# gps-breakout-mk-1_0.net
KiCad netlist of a schematic drawn in EAGLE
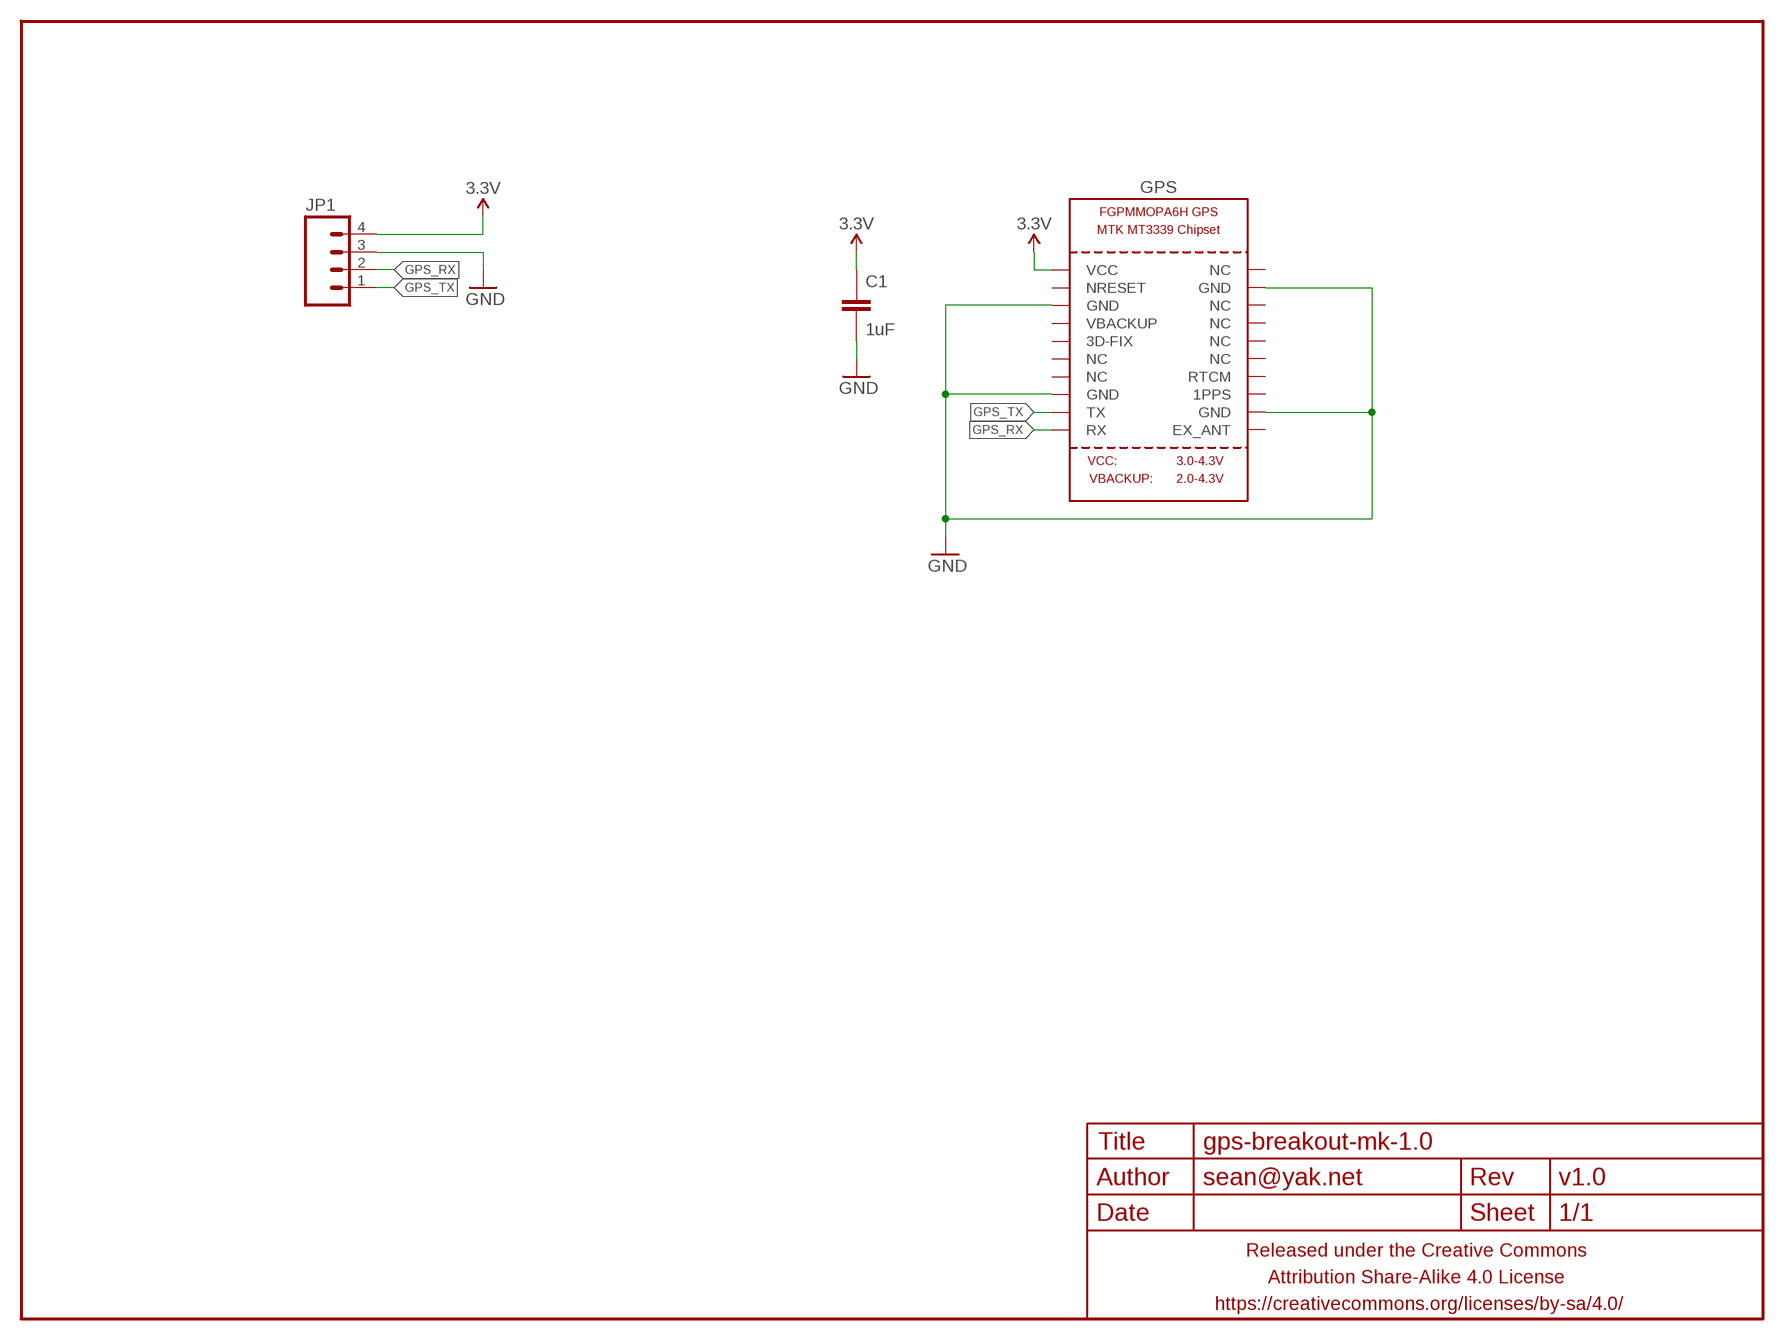
[diagram p0: schematic, sheet 1]

(export (version "E")
  (design (tool "Eeschema 10.0.6"))
  (components
    (comp (ref "C1")
      (value "1uF")
      (footprint "eagle-import:C0603")
      (libsource (lib "eagle-import") (part "CAPACITOR-CERAMICC0603"))
    )
    (comp (ref "FRAME1")
      (value "FRAME-LETTERNO_PACKAGE")
      (footprint "eagle-import:DUMMY")
      (fields (field (name "DESIGNER") "sean@yak.net") (field (name "VERSION") "v1.0"))
      (libsource (lib "eagle-import") (part "FRAME-LETTERNO_PACKAGE"))
    )
    (comp (ref "GPS")
      (value "GPS_FGPMMOPA6H")
      (footprint "eagle-import:FGPMMOPA6H")
      (libsource (lib "eagle-import") (part "GPS_FGPMMOPA6H"))
    )
    (comp (ref "JP1")
      (value "M04PTH-NS-CENTERED")
      (footprint "eagle-import:1X04-PTH-VERT-NS-CENTERED")
      (libsource (lib "eagle-import") (part "M04PTH-NS-CENTERED"))
    )
  )
  (nets
    (net (code "1") (name "3.3V") (class "Default")
      (node (ref "C1") (pin "1") (pinfunction "1_1") (pintype "passive"))
      (node (ref "GPS") (pin "P$1") (pinfunction "VCC_P$1") (pintype "bidirectional"))
      (node (ref "JP1") (pin "4") (pinfunction "4_4") (pintype "passive"))
    )
    (net (code "2") (name "GND") (class "Default")
      (node (ref "C1") (pin "2") (pinfunction "2_2") (pintype "passive"))
      (node (ref "GPS") (pin "P$12") (pinfunction "GND_P$12") (pintype "bidirectional"))
      (node (ref "GPS") (pin "P$19") (pinfunction "GND_P$19") (pintype "bidirectional"))
      (node (ref "GPS") (pin "P$3") (pinfunction "GND_P$3") (pintype "bidirectional"))
      (node (ref "GPS") (pin "P$8") (pinfunction "GND_P$8") (pintype "bidirectional"))
      (node (ref "JP1") (pin "3") (pinfunction "3_3") (pintype "passive"))
    )
    (net (code "3") (name "GPS_RX") (class "Default")
      (node (ref "GPS") (pin "P$10") (pinfunction "RX_P$10") (pintype "bidirectional"))
      (node (ref "JP1") (pin "2") (pinfunction "2_2") (pintype "passive"))
    )
    (net (code "4") (name "GPS_TX") (class "Default")
      (node (ref "GPS") (pin "P$9") (pinfunction "TX_P$9") (pintype "bidirectional"))
      (node (ref "JP1") (pin "1") (pinfunction "1_1") (pintype "passive"))
    )
    (net (code "5") (name "unconnected-(GPS-1PPS-PadP$13)") (class "Default")
      (node (ref "GPS") (pin "P$13") (pinfunction "1PPS_P$13") (pintype "bidirectional"))
    )
    (net (code "6") (name "unconnected-(GPS-3D-FIX-PadP$5)") (class "Default")
      (node (ref "GPS") (pin "P$5") (pinfunction "3D-FIX_P$5") (pintype "bidirectional"))
    )
    (net (code "7") (name "unconnected-(GPS-EX_ANT-PadP$11)") (class "Default")
      (node (ref "GPS") (pin "P$11") (pinfunction "EX_ANT_P$11") (pintype "bidirectional"))
    )
    (net (code "8") (name "unconnected-(GPS-NC-PadP$6)") (class "Default")
      (node (ref "GPS") (pin "P$6") (pinfunction "NC_P$6") (pintype "bidirectional"))
    )
    (net (code "9") (name "unconnected-(GPS-NC-PadP$7)") (class "Default")
      (node (ref "GPS") (pin "P$7") (pinfunction "NC_P$7") (pintype "bidirectional"))
    )
    (net (code "10") (name "unconnected-(GPS-NC-PadP$15)") (class "Default")
      (node (ref "GPS") (pin "P$15") (pinfunction "NC_P$15") (pintype "bidirectional"))
    )
    (net (code "11") (name "unconnected-(GPS-NC-PadP$16)") (class "Default")
      (node (ref "GPS") (pin "P$16") (pinfunction "NC_P$16") (pintype "bidirectional"))
    )
    (net (code "12") (name "unconnected-(GPS-NC-PadP$17)") (class "Default")
      (node (ref "GPS") (pin "P$17") (pinfunction "NC_P$17") (pintype "bidirectional"))
    )
    (net (code "13") (name "unconnected-(GPS-NC-PadP$18)") (class "Default")
      (node (ref "GPS") (pin "P$18") (pinfunction "NC_P$18") (pintype "bidirectional"))
    )
    (net (code "14") (name "unconnected-(GPS-NC-PadP$20)") (class "Default")
      (node (ref "GPS") (pin "P$20") (pinfunction "NC_P$20") (pintype "bidirectional"))
    )
    (net (code "15") (name "unconnected-(GPS-NRESET-PadP$2)") (class "Default")
      (node (ref "GPS") (pin "P$2") (pinfunction "NRESET_P$2") (pintype "bidirectional"))
    )
    (net (code "16") (name "unconnected-(GPS-RTCM-PadP$14)") (class "Default")
      (node (ref "GPS") (pin "P$14") (pinfunction "RTCM_P$14") (pintype "bidirectional"))
    )
    (net (code "17") (name "unconnected-(GPS-VBACKUP-PadP$4)") (class "Default")
      (node (ref "GPS") (pin "P$4") (pinfunction "VBACKUP_P$4") (pintype "bidirectional"))
    )
  )
)
